# USBasp.net
KiCad netlist of a schematic drawn in EAGLE
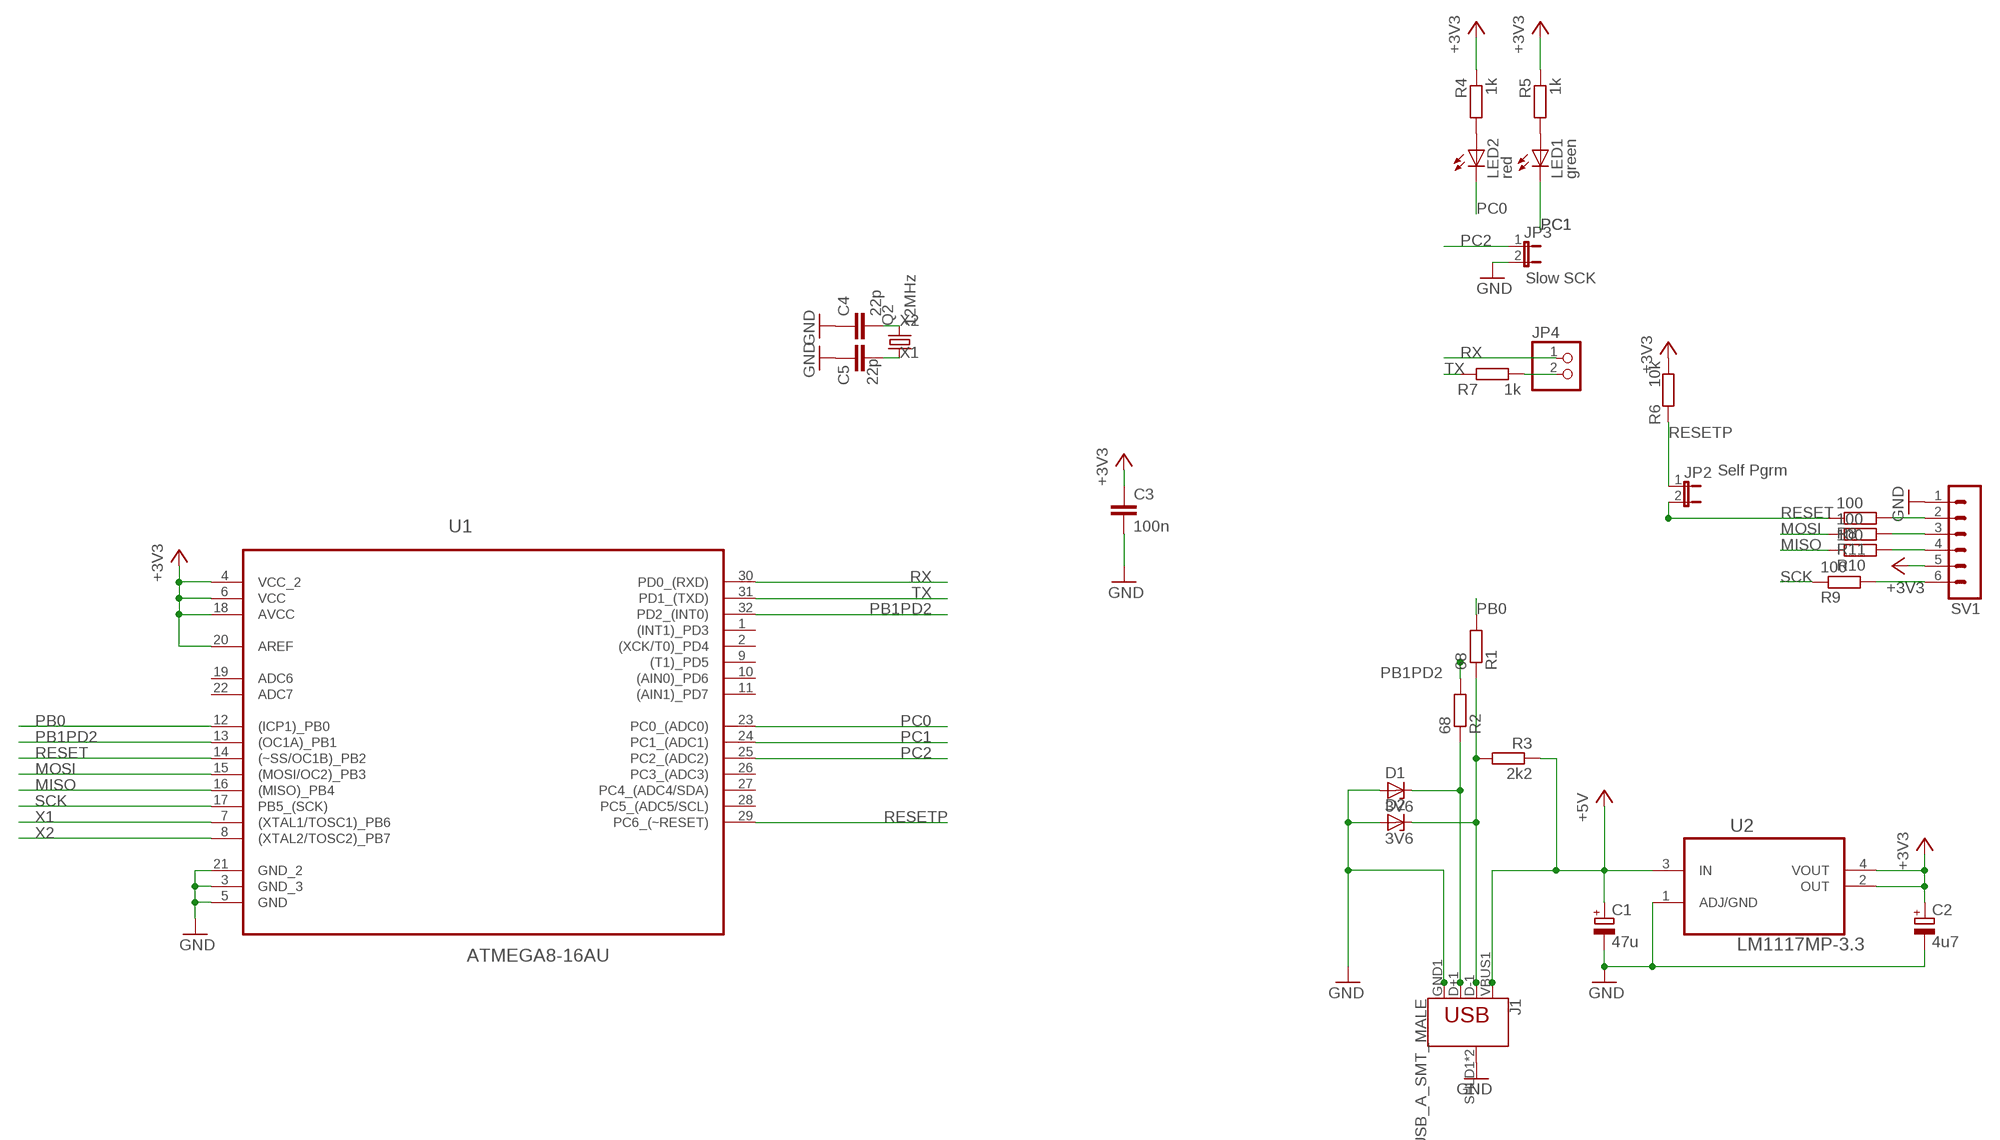
[diagram p0: schematic, sheet 1]

(export (version "E")
  (design (tool "Eeschema 10.0.6"))
  (components
    (comp (ref "C1")
      (value "47u")
      (footprint "eagle-import:ETR4")
      (libsource (lib "eagle-import") (part "CPOL-EUETR4"))
    )
    (comp (ref "C2")
      (value "4u7")
      (footprint "eagle-import:E2,5-5")
      (libsource (lib "eagle-import") (part "CPOL-EUE2.5-5"))
    )
    (comp (ref "C3")
      (value "100n")
      (footprint "eagle-import:C0603")
      (libsource (lib "eagle-import") (part "C-EUC0603"))
    )
    (comp (ref "C4")
      (value "22p")
      (footprint "eagle-import:C0603")
      (libsource (lib "eagle-import") (part "C-EUC0603"))
    )
    (comp (ref "C5")
      (value "22p")
      (footprint "eagle-import:C0504")
      (libsource (lib "eagle-import") (part "C-EUC0504"))
    )
    (comp (ref "D1")
      (value "3V6")
      (footprint "eagle-import:SOD80C")
      (libsource (lib "eagle-import") (part "ZENER-DIODESOD80C"))
    )
    (comp (ref "D2")
      (value "3V6")
      (footprint "eagle-import:SOD80C")
      (libsource (lib "eagle-import") (part "ZENER-DIODESOD80C"))
    )
    (comp (ref "J1")
      (value "USB_A_SMT_MALE")
      (footprint "eagle-import:USB-A-SMT-MALE")
      (libsource (lib "eagle-import") (part "USB_A_SMT_MALE"))
    )
    (comp (ref "JP2")
      (value "Self Pgrm")
      (footprint "eagle-import:JP1")
      (libsource (lib "eagle-import") (part "JP1E"))
    )
    (comp (ref "JP3")
      (value "Slow SCK")
      (footprint "eagle-import:JP1")
      (libsource (lib "eagle-import") (part "JP1E"))
    )
    (comp (ref "JP4")
      (value "PINHD-1X2")
      (footprint "eagle-import:1X02")
      (libsource (lib "eagle-import") (part "PINHD-1X2"))
    )
    (comp (ref "LED1")
      (value "green")
      (footprint "eagle-import:CHIP-LED0603")
      (libsource (lib "eagle-import") (part "LEDCHIP-LED0603"))
    )
    (comp (ref "LED2")
      (value "red")
      (footprint "eagle-import:CHIP-LED0603")
      (libsource (lib "eagle-import") (part "LEDCHIP-LED0603"))
    )
    (comp (ref "Q2")
      (value "12MHz")
      (footprint "eagle-import:HC49_S")
      (libsource (lib "eagle-import") (part "CRYSTALHC49S"))
    )
    (comp (ref "R1")
      (value "68")
      (footprint "eagle-import:R0603")
      (libsource (lib "eagle-import") (part "R-EU_R0603"))
    )
    (comp (ref "R2")
      (value "68")
      (footprint "eagle-import:R0603")
      (libsource (lib "eagle-import") (part "R-EU_R0603"))
    )
    (comp (ref "R3")
      (value "2k2")
      (footprint "eagle-import:R0603")
      (libsource (lib "eagle-import") (part "R-EU_R0603"))
    )
    (comp (ref "R4")
      (value "1k")
      (footprint "eagle-import:R0603")
      (libsource (lib "eagle-import") (part "R-EU_R0603"))
    )
    (comp (ref "R5")
      (value "1k")
      (footprint "eagle-import:R0603")
      (libsource (lib "eagle-import") (part "R-EU_R0603"))
    )
    (comp (ref "R6")
      (value "10k")
      (footprint "eagle-import:R0603")
      (libsource (lib "eagle-import") (part "R-EU_R0603"))
    )
    (comp (ref "R7")
      (value "1k")
      (footprint "eagle-import:R0603")
      (libsource (lib "eagle-import") (part "R-EU_R0603"))
    )
    (comp (ref "R8")
      (value "100")
      (footprint "eagle-import:R0603")
      (libsource (lib "eagle-import") (part "R-EU_R0603"))
    )
    (comp (ref "R9")
      (value "100")
      (footprint "eagle-import:R0603")
      (libsource (lib "eagle-import") (part "R-EU_R0603"))
    )
    (comp (ref "R10")
      (value "100")
      (footprint "eagle-import:R0603")
      (libsource (lib "eagle-import") (part "R-EU_R0603"))
    )
    (comp (ref "R11")
      (value "100")
      (footprint "eagle-import:R0603")
      (libsource (lib "eagle-import") (part "R-EU_R0603"))
    )
    (comp (ref "SV1")
      (value "MA06-1")
      (footprint "eagle-import:MA06-1")
      (libsource (lib "eagle-import") (part "MA06-1"))
    )
    (comp (ref "U1")
      (value "ATMEGA8-16AU")
      (footprint "eagle-import:QFP80P900X900X120-32N")
      (libsource (lib "eagle-import") (part "ATMEGA8-16AU"))
    )
    (comp (ref "U2")
      (value "LM1117MP-3.3")
      (footprint "eagle-import:SOT230P696X180-4N")
      (libsource (lib "eagle-import") (part "LM1117MP-3.3"))
    )
  )
  (nets
    (net (code "1") (name "+3V3") (class "Default")
      (node (ref "C2") (pin "+") (pinfunction "+_+") (pintype "passive"))
      (node (ref "C3") (pin "1") (pinfunction "1_1") (pintype "passive"))
      (node (ref "R4") (pin "1") (pinfunction "1_1") (pintype "passive"))
      (node (ref "R5") (pin "1") (pinfunction "1_1") (pintype "passive"))
      (node (ref "R6") (pin "1") (pinfunction "1_1") (pintype "passive"))
      (node (ref "SV1") (pin "5") (pinfunction "5_5") (pintype "passive"))
      (node (ref "U1") (pin "18") (pinfunction "AVCC_18") (pintype "power_in"))
      (node (ref "U1") (pin "20") (pinfunction "AREF_20") (pintype "input"))
      (node (ref "U1") (pin "4") (pinfunction "VCC_2_4") (pintype "power_in"))
      (node (ref "U1") (pin "6") (pinfunction "VCC_6") (pintype "power_in"))
      (node (ref "U2") (pin "2") (pinfunction "OUT_2") (pintype "output"))
      (node (ref "U2") (pin "4") (pinfunction "VOUT_4") (pintype "output"))
    )
    (net (code "2") (name "+5V") (class "Default")
      (node (ref "C1") (pin "+") (pinfunction "+_+") (pintype "passive"))
      (node (ref "J1") (pin "VBUS1") (pinfunction "VBUS_VBUS1") (pintype "power_in"))
      (node (ref "R3") (pin "1") (pinfunction "1_1") (pintype "passive"))
      (node (ref "U2") (pin "3") (pinfunction "IN_3") (pintype "input"))
    )
    (net (code "3") (name "/MISO") (class "Default")
      (node (ref "R10") (pin "1") (pinfunction "1_1") (pintype "passive"))
      (node (ref "U1") (pin "16") (pinfunction "(MISO)_PB4_16") (pintype "bidirectional"))
    )
    (net (code "4") (name "/MOSI") (class "Default")
      (node (ref "R11") (pin "1") (pinfunction "1_1") (pintype "passive"))
      (node (ref "U1") (pin "15") (pinfunction "(MOSI/OC2)_PB3_15") (pintype "bidirectional"))
    )
    (net (code "5") (name "/PB0") (class "Default")
      (node (ref "R1") (pin "2") (pinfunction "2_2") (pintype "passive"))
      (node (ref "U1") (pin "12") (pinfunction "(ICP1)_PB0_12") (pintype "bidirectional"))
    )
    (net (code "6") (name "/PB1PD2") (class "Default")
      (node (ref "R2") (pin "2") (pinfunction "2_2") (pintype "passive"))
      (node (ref "U1") (pin "13") (pinfunction "(OC1A)_PB1_13") (pintype "bidirectional"))
      (node (ref "U1") (pin "32") (pinfunction "PD2_(INT0)_32") (pintype "bidirectional"))
    )
    (net (code "7") (name "/PC0") (class "Default")
      (node (ref "LED2") (pin "C") (pinfunction "C_C") (pintype "passive"))
      (node (ref "U1") (pin "23") (pinfunction "PC0_(ADC0)_23") (pintype "bidirectional"))
    )
    (net (code "8") (name "/PC1") (class "Default")
      (node (ref "LED1") (pin "C") (pinfunction "C_C") (pintype "passive"))
      (node (ref "U1") (pin "24") (pinfunction "PC1_(ADC1)_24") (pintype "bidirectional"))
    )
    (net (code "9") (name "/PC2") (class "Default")
      (node (ref "JP3") (pin "1") (pinfunction "1_1") (pintype "passive"))
      (node (ref "U1") (pin "25") (pinfunction "PC2_(ADC2)_25") (pintype "bidirectional"))
    )
    (net (code "10") (name "/RESET") (class "Default")
      (node (ref "JP2") (pin "2") (pinfunction "2_2") (pintype "passive"))
      (node (ref "R8") (pin "1") (pinfunction "1_1") (pintype "passive"))
      (node (ref "U1") (pin "14") (pinfunction "(~{SS/OC1B})_PB2_14") (pintype "bidirectional"))
    )
    (net (code "11") (name "/RESETP") (class "Default")
      (node (ref "JP2") (pin "1") (pinfunction "1_1") (pintype "passive"))
      (node (ref "R6") (pin "2") (pinfunction "2_2") (pintype "passive"))
      (node (ref "U1") (pin "29") (pinfunction "PC6_(~{RESET})_29") (pintype "bidirectional"))
    )
    (net (code "12") (name "/RX") (class "Default")
      (node (ref "JP4") (pin "1") (pinfunction "1_1") (pintype "passive"))
      (node (ref "U1") (pin "30") (pinfunction "PD0_(RXD)_30") (pintype "bidirectional"))
    )
    (net (code "13") (name "/SCK") (class "Default")
      (node (ref "R9") (pin "1") (pinfunction "1_1") (pintype "passive"))
      (node (ref "U1") (pin "17") (pinfunction "PB5_(SCK)_17") (pintype "bidirectional"))
    )
    (net (code "14") (name "/TX") (class "Default")
      (node (ref "R7") (pin "2") (pinfunction "2_2") (pintype "passive"))
      (node (ref "U1") (pin "31") (pinfunction "PD1_(TXD)_31") (pintype "bidirectional"))
    )
    (net (code "15") (name "/X1") (class "Default")
      (node (ref "C5") (pin "2") (pinfunction "2_2") (pintype "passive"))
      (node (ref "Q2") (pin "1") (pinfunction "1_1") (pintype "passive"))
      (node (ref "U1") (pin "7") (pinfunction "(XTAL1/TOSC1)_PB6_7") (pintype "bidirectional"))
    )
    (net (code "16") (name "/X2") (class "Default")
      (node (ref "C4") (pin "2") (pinfunction "2_2") (pintype "passive"))
      (node (ref "Q2") (pin "2") (pinfunction "2_2") (pintype "passive"))
      (node (ref "U1") (pin "8") (pinfunction "(XTAL2/TOSC2)_PB7_8") (pintype "bidirectional"))
    )
    (net (code "17") (name "GND") (class "Default")
      (node (ref "C1") (pin "-") (pinfunction "-_-") (pintype "passive"))
      (node (ref "C2") (pin "-") (pinfunction "-_-") (pintype "passive"))
      (node (ref "C3") (pin "2") (pinfunction "2_2") (pintype "passive"))
      (node (ref "C4") (pin "1") (pinfunction "1_1") (pintype "passive"))
      (node (ref "C5") (pin "1") (pinfunction "1_1") (pintype "passive"))
      (node (ref "D1") (pin "A") (pinfunction "A_A") (pintype "passive"))
      (node (ref "D2") (pin "A") (pinfunction "A_A") (pintype "passive"))
      (node (ref "J1") (pin "GND1") (pinfunction "GND_GND1") (pintype "power_in"))
      (node (ref "J1") (pin "SHLD1") (pinfunction "SHIELD_SHLD1") (pintype "bidirectional"))
      (node (ref "J1") (pin "SHLD2") (pinfunction "SHIELD_SHLD2") (pintype "bidirectional"))
      (node (ref "JP3") (pin "2") (pinfunction "2_2") (pintype "passive"))
      (node (ref "SV1") (pin "1") (pinfunction "1_1") (pintype "passive"))
      (node (ref "U1") (pin "21") (pinfunction "GND_2_21") (pintype "passive"))
      (node (ref "U1") (pin "3") (pinfunction "GND_3_3") (pintype "passive"))
      (node (ref "U1") (pin "5") (pinfunction "GND_5") (pintype "passive"))
      (node (ref "U2") (pin "1") (pinfunction "ADJ/GND_1") (pintype "passive"))
    )
    (net (code "18") (name "Net-(J1-D+)") (class "Default")
      (node (ref "D1") (pin "C") (pinfunction "C_C") (pintype "passive"))
      (node (ref "J1") (pin "D+1") (pinfunction "D+_D+1") (pintype "bidirectional"))
      (node (ref "R2") (pin "1") (pinfunction "1_1") (pintype "passive"))
    )
    (net (code "19") (name "Net-(J1-D-)") (class "Default")
      (node (ref "D2") (pin "C") (pinfunction "C_C") (pintype "passive"))
      (node (ref "J1") (pin "D-1") (pinfunction "D-_D-1") (pintype "bidirectional"))
      (node (ref "R1") (pin "1") (pinfunction "1_1") (pintype "passive"))
      (node (ref "R3") (pin "2") (pinfunction "2_2") (pintype "passive"))
    )
    (net (code "20") (name "Net-(JP4-Pad2)") (class "Default")
      (node (ref "JP4") (pin "2") (pinfunction "2_2") (pintype "passive"))
      (node (ref "R7") (pin "1") (pinfunction "1_1") (pintype "passive"))
    )
    (net (code "21") (name "Net-(LED1-PadA)") (class "Default")
      (node (ref "LED1") (pin "A") (pinfunction "A_A") (pintype "passive"))
      (node (ref "R5") (pin "2") (pinfunction "2_2") (pintype "passive"))
    )
    (net (code "22") (name "Net-(LED2-PadA)") (class "Default")
      (node (ref "LED2") (pin "A") (pinfunction "A_A") (pintype "passive"))
      (node (ref "R4") (pin "2") (pinfunction "2_2") (pintype "passive"))
    )
    (net (code "23") (name "Net-(R8-Pad2)") (class "Default")
      (node (ref "R8") (pin "2") (pinfunction "2_2") (pintype "passive"))
      (node (ref "SV1") (pin "2") (pinfunction "2_2") (pintype "passive"))
    )
    (net (code "24") (name "Net-(R9-Pad2)") (class "Default")
      (node (ref "R9") (pin "2") (pinfunction "2_2") (pintype "passive"))
      (node (ref "SV1") (pin "6") (pinfunction "6_6") (pintype "passive"))
    )
    (net (code "25") (name "Net-(R10-Pad2)") (class "Default")
      (node (ref "R10") (pin "2") (pinfunction "2_2") (pintype "passive"))
      (node (ref "SV1") (pin "4") (pinfunction "4_4") (pintype "passive"))
    )
    (net (code "26") (name "Net-(R11-Pad2)") (class "Default")
      (node (ref "R11") (pin "2") (pinfunction "2_2") (pintype "passive"))
      (node (ref "SV1") (pin "3") (pinfunction "3_3") (pintype "passive"))
    )
    (net (code "27") (name "unconnected-(U1-(AIN0)_PD6-Pad10)") (class "Default")
      (node (ref "U1") (pin "10") (pinfunction "(AIN0)_PD6_10") (pintype "bidirectional"))
    )
    (net (code "28") (name "unconnected-(U1-(AIN1)_PD7-Pad11)") (class "Default")
      (node (ref "U1") (pin "11") (pinfunction "(AIN1)_PD7_11") (pintype "bidirectional"))
    )
    (net (code "29") (name "unconnected-(U1-(INT1)_PD3-Pad1)") (class "Default")
      (node (ref "U1") (pin "1") (pinfunction "(INT1)_PD3_1") (pintype "bidirectional"))
    )
    (net (code "30") (name "unconnected-(U1-(T1)_PD5-Pad9)") (class "Default")
      (node (ref "U1") (pin "9") (pinfunction "(T1)_PD5_9") (pintype "bidirectional"))
    )
    (net (code "31") (name "unconnected-(U1-(XCK{slash}T0)_PD4-Pad2)") (class "Default")
      (node (ref "U1") (pin "2") (pinfunction "(XCK/T0)_PD4_2") (pintype "bidirectional"))
    )
    (net (code "32") (name "unconnected-(U1-ADC6-Pad19)") (class "Default")
      (node (ref "U1") (pin "19") (pinfunction "ADC6_19") (pintype "input"))
    )
    (net (code "33") (name "unconnected-(U1-ADC7-Pad22)") (class "Default")
      (node (ref "U1") (pin "22") (pinfunction "ADC7_22") (pintype "input"))
    )
    (net (code "34") (name "unconnected-(U1-PC3_(ADC3)-Pad26)") (class "Default")
      (node (ref "U1") (pin "26") (pinfunction "PC3_(ADC3)_26") (pintype "bidirectional"))
    )
    (net (code "35") (name "unconnected-(U1-PC4_(ADC4{slash}SDA)-Pad27)") (class "Default")
      (node (ref "U1") (pin "27") (pinfunction "PC4_(ADC4/SDA)_27") (pintype "bidirectional"))
    )
    (net (code "36") (name "unconnected-(U1-PC5_(ADC5{slash}SCL)-Pad28)") (class "Default")
      (node (ref "U1") (pin "28") (pinfunction "PC5_(ADC5/SCL)_28") (pintype "bidirectional"))
    )
  )
)
